# CROSSOVER_MONO_FINISHED_KRE_rev3_dec.net
KiCad netlist of a schematic drawn in EAGLE
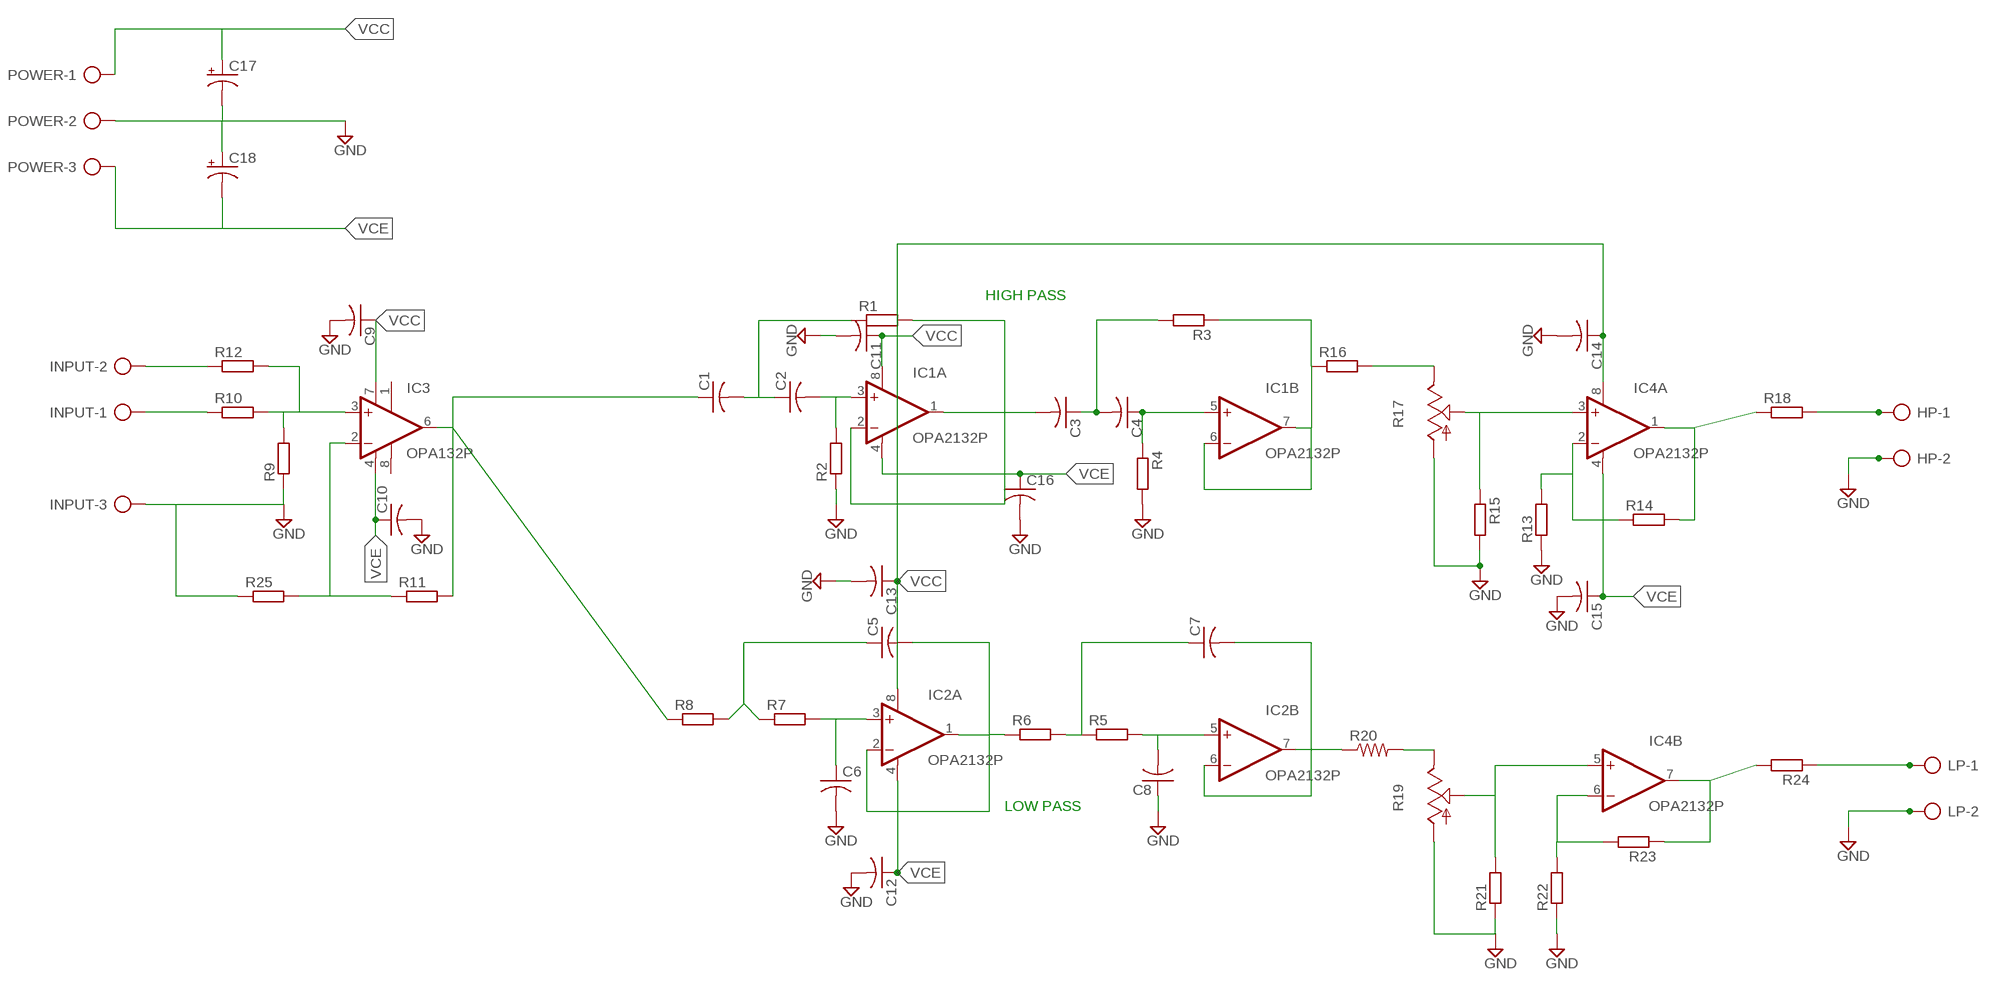
[diagram p0: schematic, sheet 1]

(export (version "E")
  (design (tool "Eeschema 10.0.6"))
  (components
    (comp (ref "C1")
      (value "C-US050-025X075")
      (footprint "eagle-import:C050-025X075")
      (libsource (lib "eagle-import") (part "C-US050-025X075"))
    )
    (comp (ref "C2")
      (value "C-US050-025X075")
      (footprint "eagle-import:C050-025X075")
      (libsource (lib "eagle-import") (part "C-US050-025X075"))
    )
    (comp (ref "C3")
      (value "C-US050-025X075")
      (footprint "eagle-import:C050-025X075")
      (libsource (lib "eagle-import") (part "C-US050-025X075"))
    )
    (comp (ref "C4")
      (value "C-US050-025X075")
      (footprint "eagle-import:C050-025X075")
      (libsource (lib "eagle-import") (part "C-US050-025X075"))
    )
    (comp (ref "C5")
      (value "C-US050-025X075")
      (footprint "eagle-import:C050-025X075")
      (libsource (lib "eagle-import") (part "C-US050-025X075"))
    )
    (comp (ref "C6")
      (value "C-US050-025X075")
      (footprint "eagle-import:C050-025X075")
      (libsource (lib "eagle-import") (part "C-US050-025X075"))
    )
    (comp (ref "C7")
      (value "C-US050-025X075")
      (footprint "eagle-import:C050-025X075")
      (libsource (lib "eagle-import") (part "C-US050-025X075"))
    )
    (comp (ref "C8")
      (value "C-US050-025X075")
      (footprint "eagle-import:C050-025X075")
      (libsource (lib "eagle-import") (part "C-US050-025X075"))
    )
    (comp (ref "C9")
      (value "C-US050-025X075")
      (footprint "eagle-import:C050-025X075")
      (libsource (lib "eagle-import") (part "C-US050-025X075"))
    )
    (comp (ref "C10")
      (value "C-US050-025X075")
      (footprint "eagle-import:C050-025X075")
      (libsource (lib "eagle-import") (part "C-US050-025X075"))
    )
    (comp (ref "C11")
      (value "C-US050-025X075")
      (footprint "eagle-import:C050-025X075")
      (libsource (lib "eagle-import") (part "C-US050-025X075"))
    )
    (comp (ref "C12")
      (value "C-US050-025X075")
      (footprint "eagle-import:C050-025X075")
      (libsource (lib "eagle-import") (part "C-US050-025X075"))
    )
    (comp (ref "C13")
      (value "C-US050-025X075")
      (footprint "eagle-import:C050-025X075")
      (libsource (lib "eagle-import") (part "C-US050-025X075"))
    )
    (comp (ref "C14")
      (value "C-US050-025X075")
      (footprint "eagle-import:C050-025X075")
      (libsource (lib "eagle-import") (part "C-US050-025X075"))
    )
    (comp (ref "C15")
      (value "C-US050-025X075")
      (footprint "eagle-import:C050-025X075")
      (libsource (lib "eagle-import") (part "C-US050-025X075"))
    )
    (comp (ref "C16")
      (value "C-US050-025X075")
      (footprint "eagle-import:C050-025X075")
      (libsource (lib "eagle-import") (part "C-US050-025X075"))
    )
    (comp (ref "C17")
      (value "CPOL-USE5-10.5")
      (footprint "eagle-import:E5-10,5")
      (libsource (lib "eagle-import") (part "CPOL-USE5-10.5"))
    )
    (comp (ref "C18")
      (value "CPOL-USE5-10.5")
      (footprint "eagle-import:E5-10,5")
      (libsource (lib "eagle-import") (part "CPOL-USE5-10.5"))
    )
    (comp (ref "HP")
      (value "KRE_2VIAS")
      (footprint "eagle-import:KRE_2VIAS")
      (libsource (lib "eagle-import") (part "KRE_2VIAS"))
    )
    (comp (ref "IC1")
      (value "OPA2132P")
      (footprint "eagle-import:DIL08")
      (libsource (lib "eagle-import") (part "OPA2132P"))
    )
    (comp (ref "IC2")
      (value "OPA2132P")
      (footprint "eagle-import:DIL08")
      (libsource (lib "eagle-import") (part "OPA2132P"))
    )
    (comp (ref "IC3")
      (value "OPA132P")
      (footprint "eagle-import:DIL08")
      (libsource (lib "eagle-import") (part "OPA132P"))
    )
    (comp (ref "IC4")
      (value "OPA2132P")
      (footprint "eagle-import:DIL08")
      (libsource (lib "eagle-import") (part "OPA2132P"))
    )
    (comp (ref "INPUT")
      (value "KRE_3VIAS")
      (footprint "eagle-import:KRE_3VIAS")
      (libsource (lib "eagle-import") (part "KRE_3VIAS"))
    )
    (comp (ref "LP")
      (value "KRE_2VIAS")
      (footprint "eagle-import:KRE_2VIAS")
      (libsource (lib "eagle-import") (part "KRE_2VIAS"))
    )
    (comp (ref "POWER")
      (value "KRE_3VIAS")
      (footprint "eagle-import:KRE_3VIAS")
      (libsource (lib "eagle-import") (part "KRE_3VIAS"))
    )
    (comp (ref "R1")
      (value "R-EU_0207/10")
      (footprint "eagle-import:0207_10")
      (libsource (lib "eagle-import") (part "R-EU_0207/10"))
    )
    (comp (ref "R2")
      (value "R-EU_0207/10")
      (footprint "eagle-import:0207_10")
      (libsource (lib "eagle-import") (part "R-EU_0207/10"))
    )
    (comp (ref "R3")
      (value "R-EU_0207/10")
      (footprint "eagle-import:0207_10")
      (libsource (lib "eagle-import") (part "R-EU_0207/10"))
    )
    (comp (ref "R4")
      (value "R-EU_0207/10")
      (footprint "eagle-import:0207_10")
      (libsource (lib "eagle-import") (part "R-EU_0207/10"))
    )
    (comp (ref "R5")
      (value "R-EU_0207/10")
      (footprint "eagle-import:0207_10")
      (libsource (lib "eagle-import") (part "R-EU_0207/10"))
    )
    (comp (ref "R6")
      (value "R-EU_0207/10")
      (footprint "eagle-import:0207_10")
      (libsource (lib "eagle-import") (part "R-EU_0207/10"))
    )
    (comp (ref "R7")
      (value "R-EU_0207/10")
      (footprint "eagle-import:0207_10")
      (libsource (lib "eagle-import") (part "R-EU_0207/10"))
    )
    (comp (ref "R8")
      (value "R-EU_0207/10")
      (footprint "eagle-import:0207_10")
      (libsource (lib "eagle-import") (part "R-EU_0207/10"))
    )
    (comp (ref "R9")
      (value "R-EU_0207/10")
      (footprint "eagle-import:0207_10")
      (libsource (lib "eagle-import") (part "R-EU_0207/10"))
    )
    (comp (ref "R10")
      (value "R-EU_0207/10")
      (footprint "eagle-import:0207_10")
      (libsource (lib "eagle-import") (part "R-EU_0207/10"))
    )
    (comp (ref "R11")
      (value "R-EU_0207/10")
      (footprint "eagle-import:0207_10")
      (libsource (lib "eagle-import") (part "R-EU_0207/10"))
    )
    (comp (ref "R12")
      (value "R-EU_0207/10")
      (footprint "eagle-import:0207_10")
      (libsource (lib "eagle-import") (part "R-EU_0207/10"))
    )
    (comp (ref "R13")
      (value "R-EU_0207/10")
      (footprint "eagle-import:0207_10")
      (libsource (lib "eagle-import") (part "R-EU_0207/10"))
    )
    (comp (ref "R14")
      (value "R-EU_0207/10")
      (footprint "eagle-import:0207_10")
      (libsource (lib "eagle-import") (part "R-EU_0207/10"))
    )
    (comp (ref "R15")
      (value "R-EU_0207/10")
      (footprint "eagle-import:0207_10")
      (libsource (lib "eagle-import") (part "R-EU_0207/10"))
    )
    (comp (ref "R16")
      (value "R-EU_0207/10")
      (footprint "eagle-import:0207_10")
      (libsource (lib "eagle-import") (part "R-EU_0207/10"))
    )
    (comp (ref "R17")
      (value "TRIM_US-RJ9W")
      (footprint "eagle-import:RJ9W")
      (libsource (lib "eagle-import") (part "TRIM_US-RJ9W"))
    )
    (comp (ref "R18")
      (value "R-EU_0207/10")
      (footprint "eagle-import:0207_10")
      (libsource (lib "eagle-import") (part "R-EU_0207/10"))
    )
    (comp (ref "R19")
      (value "TRIM_US-RJ9W")
      (footprint "eagle-import:RJ9W")
      (libsource (lib "eagle-import") (part "TRIM_US-RJ9W"))
    )
    (comp (ref "R20")
      (value "R-US_0204/7")
      (footprint "eagle-import:0204_7")
      (libsource (lib "eagle-import") (part "R-US_0204/7"))
    )
    (comp (ref "R21")
      (value "R-EU_0207/10")
      (footprint "eagle-import:0207_10")
      (libsource (lib "eagle-import") (part "R-EU_0207/10"))
    )
    (comp (ref "R22")
      (value "R-EU_0207/10")
      (footprint "eagle-import:0207_10")
      (libsource (lib "eagle-import") (part "R-EU_0207/10"))
    )
    (comp (ref "R23")
      (value "R-EU_0207/10")
      (footprint "eagle-import:0207_10")
      (libsource (lib "eagle-import") (part "R-EU_0207/10"))
    )
    (comp (ref "R24")
      (value "R-EU_0207/10")
      (footprint "eagle-import:0207_10")
      (libsource (lib "eagle-import") (part "R-EU_0207/10"))
    )
    (comp (ref "R25")
      (value "R-EU_0207/10")
      (footprint "eagle-import:0207_10")
      (libsource (lib "eagle-import") (part "R-EU_0207/10"))
    )
  )
  (nets
    (net (code "1") (name "GND") (class "Default")
      (node (ref "C10") (pin "2") (pinfunction "2_2") (pintype "passive"))
      (node (ref "C11") (pin "2") (pinfunction "2_2") (pintype "passive"))
      (node (ref "C12") (pin "2") (pinfunction "2_2") (pintype "passive"))
      (node (ref "C13") (pin "2") (pinfunction "2_2") (pintype "passive"))
      (node (ref "C14") (pin "2") (pinfunction "2_2") (pintype "passive"))
      (node (ref "C15") (pin "2") (pinfunction "2_2") (pintype "passive"))
      (node (ref "C16") (pin "2") (pinfunction "2_2") (pintype "passive"))
      (node (ref "C17") (pin "-") (pinfunction "-_-") (pintype "passive"))
      (node (ref "C18") (pin "+") (pinfunction "+_+") (pintype "passive"))
      (node (ref "C6") (pin "2") (pinfunction "2_2") (pintype "passive"))
      (node (ref "C8") (pin "1") (pinfunction "1_1") (pintype "passive"))
      (node (ref "C9") (pin "2") (pinfunction "2_2") (pintype "passive"))
      (node (ref "HP") (pin "2") (pinfunction "KL_2") (pintype "passive"))
      (node (ref "INPUT") (pin "3") (pinfunction "KL_3") (pintype "passive"))
      (node (ref "LP") (pin "2") (pinfunction "KL_2") (pintype "passive"))
      (node (ref "POWER") (pin "2") (pinfunction "KL_2") (pintype "passive"))
      (node (ref "R13") (pin "1") (pinfunction "1_1") (pintype "passive"))
      (node (ref "R15") (pin "2") (pinfunction "2_2") (pintype "passive"))
      (node (ref "R17") (pin "A") (pinfunction "A_A") (pintype "passive"))
      (node (ref "R19") (pin "A") (pinfunction "A_A") (pintype "passive"))
      (node (ref "R2") (pin "1") (pinfunction "1_1") (pintype "passive"))
      (node (ref "R21") (pin "1") (pinfunction "1_1") (pintype "passive"))
      (node (ref "R22") (pin "1") (pinfunction "1_1") (pintype "passive"))
      (node (ref "R25") (pin "1") (pinfunction "1_1") (pintype "passive"))
      (node (ref "R4") (pin "2") (pinfunction "2_2") (pintype "passive"))
      (node (ref "R9") (pin "1") (pinfunction "1_1") (pintype "passive"))
    )
    (net (code "2") (name "Net-(C1-Pad2)") (class "Default")
      (node (ref "C1") (pin "2") (pinfunction "2_2") (pintype "passive"))
      (node (ref "C2") (pin "1") (pinfunction "1_1") (pintype "passive"))
      (node (ref "R1") (pin "1") (pinfunction "1_1") (pintype "passive"))
    )
    (net (code "3") (name "Net-(C3-Pad1)") (class "Default")
      (node (ref "C3") (pin "1") (pinfunction "1_1") (pintype "passive"))
      (node (ref "C4") (pin "2") (pinfunction "2_2") (pintype "passive"))
      (node (ref "R3") (pin "2") (pinfunction "2_2") (pintype "passive"))
    )
    (net (code "4") (name "Net-(C5-Pad1)") (class "Default")
      (node (ref "C5") (pin "1") (pinfunction "1_1") (pintype "passive"))
      (node (ref "R7") (pin "1") (pinfunction "1_1") (pintype "passive"))
      (node (ref "R8") (pin "2") (pinfunction "2_2") (pintype "passive"))
    )
    (net (code "5") (name "Net-(C7-Pad1)") (class "Default")
      (node (ref "C7") (pin "1") (pinfunction "1_1") (pintype "passive"))
      (node (ref "R5") (pin "1") (pinfunction "1_1") (pintype "passive"))
      (node (ref "R6") (pin "2") (pinfunction "2_2") (pintype "passive"))
    )
    (net (code "6") (name "Net-(HPA-KL)") (class "Default")
      (node (ref "HP") (pin "1") (pinfunction "KL_1") (pintype "passive"))
      (node (ref "R18") (pin "2") (pinfunction "2_2") (pintype "passive"))
    )
    (net (code "7") (name "Net-(IC1A-+IN)") (class "Default")
      (node (ref "C2") (pin "2") (pinfunction "2_2") (pintype "passive"))
      (node (ref "IC1") (pin "3") (pinfunction "+IN_3") (pintype "input"))
      (node (ref "R2") (pin "2") (pinfunction "2_2") (pintype "passive"))
    )
    (net (code "8") (name "Net-(IC1A--IN)") (class "Default")
      (node (ref "C3") (pin "2") (pinfunction "2_2") (pintype "passive"))
      (node (ref "IC1") (pin "1") (pinfunction "OUT_1") (pintype "output"))
      (node (ref "IC1") (pin "2") (pinfunction "-IN_2") (pintype "input"))
      (node (ref "R1") (pin "2") (pinfunction "2_2") (pintype "passive"))
    )
    (net (code "9") (name "Net-(IC1B-+IN)") (class "Default")
      (node (ref "C4") (pin "1") (pinfunction "1_1") (pintype "passive"))
      (node (ref "IC1") (pin "5") (pinfunction "+IN_5") (pintype "input"))
      (node (ref "R4") (pin "1") (pinfunction "1_1") (pintype "passive"))
    )
    (net (code "10") (name "Net-(IC1B--IN)") (class "Default")
      (node (ref "IC1") (pin "6") (pinfunction "-IN_6") (pintype "input"))
      (node (ref "IC1") (pin "7") (pinfunction "OUT_7") (pintype "output"))
      (node (ref "R16") (pin "1") (pinfunction "1_1") (pintype "passive"))
      (node (ref "R3") (pin "1") (pinfunction "1_1") (pintype "passive"))
    )
    (net (code "11") (name "Net-(IC2A-+IN)") (class "Default")
      (node (ref "C6") (pin "1") (pinfunction "1_1") (pintype "passive"))
      (node (ref "IC2") (pin "3") (pinfunction "+IN_3") (pintype "input"))
      (node (ref "R7") (pin "2") (pinfunction "2_2") (pintype "passive"))
    )
    (net (code "12") (name "Net-(IC2A--IN)") (class "Default")
      (node (ref "C5") (pin "2") (pinfunction "2_2") (pintype "passive"))
      (node (ref "IC2") (pin "1") (pinfunction "OUT_1") (pintype "output"))
      (node (ref "IC2") (pin "2") (pinfunction "-IN_2") (pintype "input"))
      (node (ref "R6") (pin "1") (pinfunction "1_1") (pintype "passive"))
    )
    (net (code "13") (name "Net-(IC2B-+IN)") (class "Default")
      (node (ref "C8") (pin "2") (pinfunction "2_2") (pintype "passive"))
      (node (ref "IC2") (pin "5") (pinfunction "+IN_5") (pintype "input"))
      (node (ref "R5") (pin "2") (pinfunction "2_2") (pintype "passive"))
    )
    (net (code "14") (name "Net-(IC2B--IN)") (class "Default")
      (node (ref "C7") (pin "2") (pinfunction "2_2") (pintype "passive"))
      (node (ref "IC2") (pin "6") (pinfunction "-IN_6") (pintype "input"))
      (node (ref "IC2") (pin "7") (pinfunction "OUT_7") (pintype "output"))
      (node (ref "R20") (pin "1") (pinfunction "1_1") (pintype "passive"))
    )
    (net (code "15") (name "Net-(IC3-+IN)") (class "Default")
      (node (ref "IC3") (pin "3") (pinfunction "+IN_3") (pintype "input"))
      (node (ref "R10") (pin "2") (pinfunction "2_2") (pintype "passive"))
      (node (ref "R12") (pin "2") (pinfunction "2_2") (pintype "passive"))
      (node (ref "R9") (pin "2") (pinfunction "2_2") (pintype "passive"))
    )
    (net (code "16") (name "Net-(IC3--IN)") (class "Default")
      (node (ref "IC3") (pin "2") (pinfunction "-IN_2") (pintype "input"))
      (node (ref "R11") (pin "1") (pinfunction "1_1") (pintype "passive"))
      (node (ref "R25") (pin "2") (pinfunction "2_2") (pintype "passive"))
    )
    (net (code "17") (name "Net-(IC3-OUT)") (class "Default")
      (node (ref "C1") (pin "1") (pinfunction "1_1") (pintype "passive"))
      (node (ref "IC3") (pin "6") (pinfunction "OUT_6") (pintype "output"))
      (node (ref "R11") (pin "2") (pinfunction "2_2") (pintype "passive"))
      (node (ref "R8") (pin "1") (pinfunction "1_1") (pintype "passive"))
    )
    (net (code "18") (name "Net-(IC4A-+IN)") (class "Default")
      (node (ref "IC4") (pin "3") (pinfunction "+IN_3") (pintype "input"))
      (node (ref "R15") (pin "1") (pinfunction "1_1") (pintype "passive"))
      (node (ref "R17") (pin "S") (pinfunction "S_S") (pintype "passive"))
    )
    (net (code "19") (name "Net-(IC4A--IN)") (class "Default")
      (node (ref "IC4") (pin "2") (pinfunction "-IN_2") (pintype "input"))
      (node (ref "R13") (pin "2") (pinfunction "2_2") (pintype "passive"))
      (node (ref "R14") (pin "1") (pinfunction "1_1") (pintype "passive"))
    )
    (net (code "20") (name "Net-(IC4A-OUT)") (class "Default")
      (node (ref "IC4") (pin "1") (pinfunction "OUT_1") (pintype "output"))
      (node (ref "R14") (pin "2") (pinfunction "2_2") (pintype "passive"))
      (node (ref "R18") (pin "1") (pinfunction "1_1") (pintype "passive"))
    )
    (net (code "21") (name "Net-(IC4B-+IN)") (class "Default")
      (node (ref "IC4") (pin "5") (pinfunction "+IN_5") (pintype "input"))
      (node (ref "R19") (pin "S") (pinfunction "S_S") (pintype "passive"))
      (node (ref "R21") (pin "2") (pinfunction "2_2") (pintype "passive"))
    )
    (net (code "22") (name "Net-(IC4B--IN)") (class "Default")
      (node (ref "IC4") (pin "6") (pinfunction "-IN_6") (pintype "input"))
      (node (ref "R22") (pin "2") (pinfunction "2_2") (pintype "passive"))
      (node (ref "R23") (pin "2") (pinfunction "2_2") (pintype "passive"))
    )
    (net (code "23") (name "Net-(IC4B-OUT)") (class "Default")
      (node (ref "IC4") (pin "7") (pinfunction "OUT_7") (pintype "output"))
      (node (ref "R23") (pin "1") (pinfunction "1_1") (pintype "passive"))
      (node (ref "R24") (pin "2") (pinfunction "2_2") (pintype "passive"))
    )
    (net (code "24") (name "Net-(INPUTA-KL)") (class "Default")
      (node (ref "INPUT") (pin "1") (pinfunction "KL_1") (pintype "passive"))
      (node (ref "R10") (pin "1") (pinfunction "1_1") (pintype "passive"))
    )
    (net (code "25") (name "Net-(INPUTB-KL)") (class "Default")
      (node (ref "INPUT") (pin "2") (pinfunction "KL_2") (pintype "passive"))
      (node (ref "R12") (pin "1") (pinfunction "1_1") (pintype "passive"))
    )
    (net (code "26") (name "Net-(LPA-KL)") (class "Default")
      (node (ref "LP") (pin "1") (pinfunction "KL_1") (pintype "passive"))
      (node (ref "R24") (pin "1") (pinfunction "1_1") (pintype "passive"))
    )
    (net (code "27") (name "Net-(R16-Pad2)") (class "Default")
      (node (ref "R16") (pin "2") (pinfunction "2_2") (pintype "passive"))
      (node (ref "R17") (pin "E") (pinfunction "E_E") (pintype "passive"))
    )
    (net (code "28") (name "Net-(R19-PadE)") (class "Default")
      (node (ref "R19") (pin "E") (pinfunction "E_E") (pintype "passive"))
      (node (ref "R20") (pin "2") (pinfunction "2_2") (pintype "passive"))
    )
    (net (code "29") (name "VCC") (class "Default")
      (node (ref "C11") (pin "1") (pinfunction "1_1") (pintype "passive"))
      (node (ref "C13") (pin "1") (pinfunction "1_1") (pintype "passive"))
      (node (ref "C14") (pin "1") (pinfunction "1_1") (pintype "passive"))
      (node (ref "C17") (pin "+") (pinfunction "+_+") (pintype "passive"))
      (node (ref "C9") (pin "1") (pinfunction "1_1") (pintype "passive"))
      (node (ref "IC1") (pin "8") (pinfunction "V+_8") (pintype "power_in"))
      (node (ref "IC2") (pin "8") (pinfunction "V+_8") (pintype "power_in"))
      (node (ref "IC3") (pin "7") (pinfunction "V+_7") (pintype "power_in"))
      (node (ref "IC4") (pin "8") (pinfunction "V+_8") (pintype "power_in"))
      (node (ref "POWER") (pin "1") (pinfunction "KL_1") (pintype "passive"))
    )
    (net (code "30") (name "VCE") (class "Default")
      (node (ref "C10") (pin "1") (pinfunction "1_1") (pintype "passive"))
      (node (ref "C12") (pin "1") (pinfunction "1_1") (pintype "passive"))
      (node (ref "C15") (pin "1") (pinfunction "1_1") (pintype "passive"))
      (node (ref "C16") (pin "1") (pinfunction "1_1") (pintype "passive"))
      (node (ref "C18") (pin "-") (pinfunction "-_-") (pintype "passive"))
      (node (ref "IC1") (pin "4") (pinfunction "V-_4") (pintype "power_in"))
      (node (ref "IC2") (pin "4") (pinfunction "V-_4") (pintype "power_in"))
      (node (ref "IC3") (pin "4") (pinfunction "V-_4") (pintype "power_in"))
      (node (ref "IC4") (pin "4") (pinfunction "V-_4") (pintype "power_in"))
      (node (ref "POWER") (pin "3") (pinfunction "KL_3") (pintype "passive"))
    )
    (net (code "31") (name "unconnected-(IC3-TRIM1-Pad1)") (class "Default")
      (node (ref "IC3") (pin "1") (pinfunction "TRIM1_1") (pintype "passive"))
    )
    (net (code "32") (name "unconnected-(IC3-TRIM2-Pad8)") (class "Default")
      (node (ref "IC3") (pin "8") (pinfunction "TRIM2_8") (pintype "passive"))
    )
  )
)
